# ALU_Flags.net
KiCad netlist of a schematic drawn in EAGLE
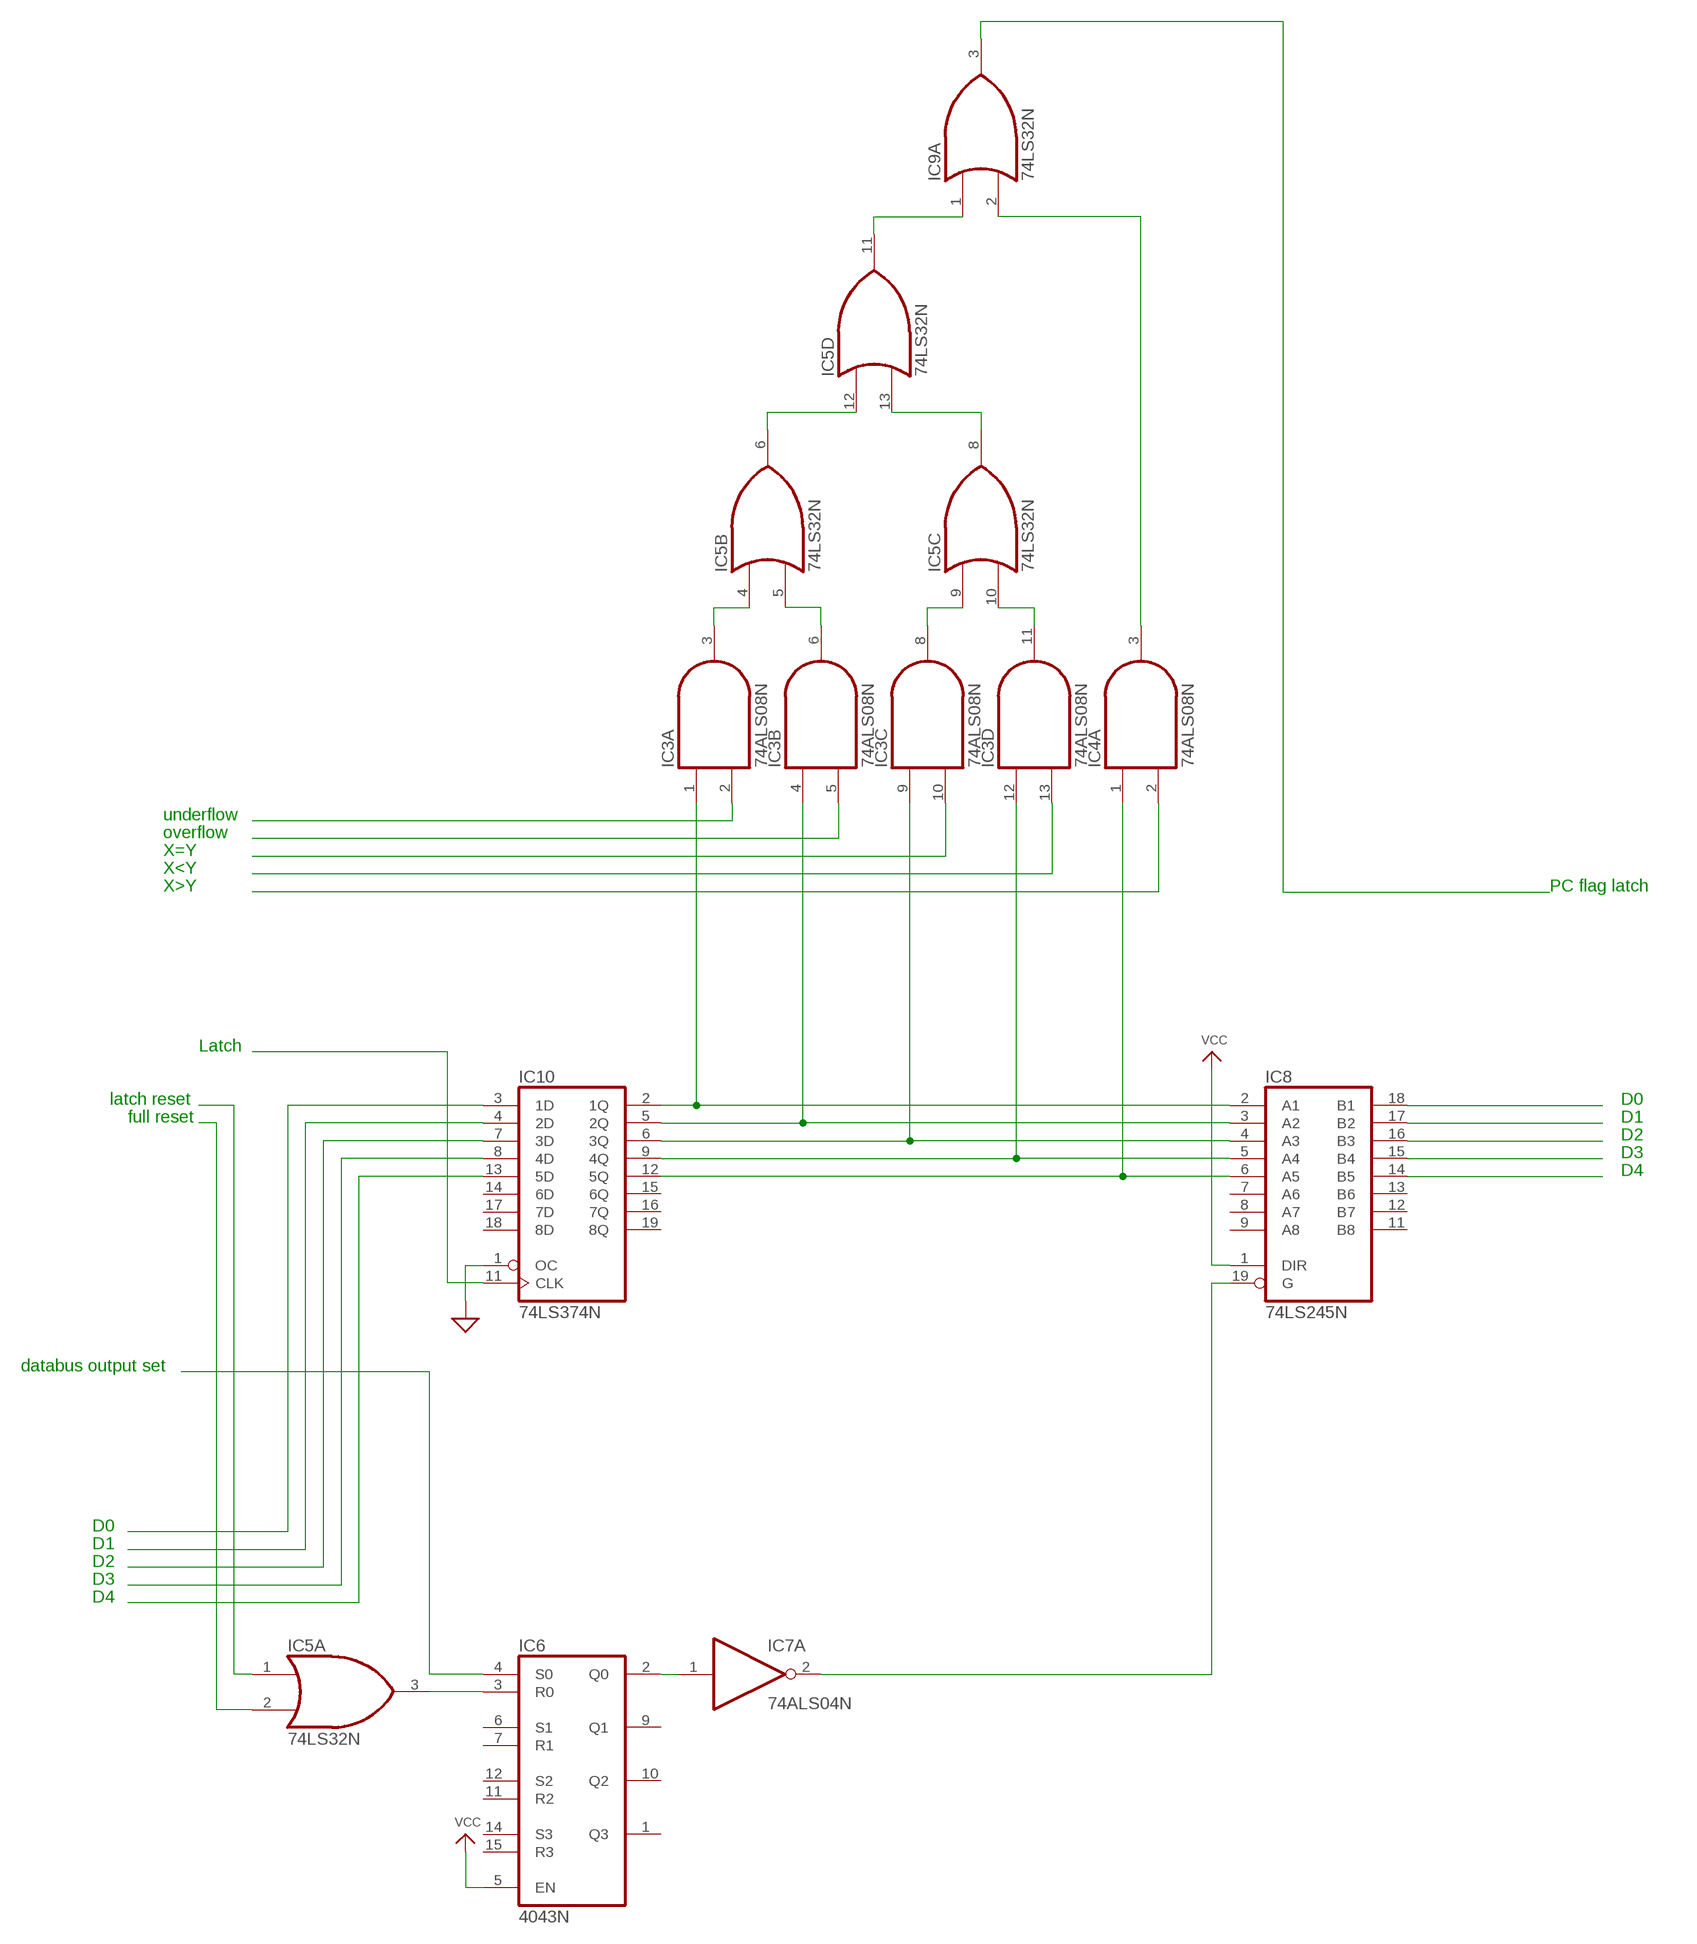
[diagram p0: schematic, sheet 1]

(export (version "E")
  (design (tool "Eeschema 10.0.6"))
  (components
    (comp (ref "IC3")
      (value "74ALS08N")
      (footprint "eagle-import:DIL14")
      (libsource (lib "eagle-import") (part "7408NALS"))
    )
    (comp (ref "IC4")
      (value "74ALS08N")
      (footprint "eagle-import:DIL14")
      (libsource (lib "eagle-import") (part "7408NALS"))
    )
    (comp (ref "IC5")
      (value "74LS32N")
      (footprint "eagle-import:DIL14")
      (libsource (lib "eagle-import") (part "7432NLS"))
    )
    (comp (ref "IC6")
      (value "4043N")
      (footprint "eagle-import:DIL16")
      (libsource (lib "eagle-import") (part "4043N"))
    )
    (comp (ref "IC7")
      (value "74ALS04N")
      (footprint "eagle-import:DIL14")
      (libsource (lib "eagle-import") (part "7404NALS"))
    )
    (comp (ref "IC8")
      (value "74LS245N")
      (footprint "eagle-import:DIL20")
      (libsource (lib "eagle-import") (part "74245NLS"))
    )
    (comp (ref "IC9")
      (value "74LS32N")
      (footprint "eagle-import:DIL14")
      (libsource (lib "eagle-import") (part "7432NLS"))
    )
    (comp (ref "IC10")
      (value "74LS374N")
      (footprint "eagle-import:DIL20")
      (libsource (lib "eagle-import") (part "74374NLS"))
    )
  )
  (nets
    (net (code "1") (name "Net-(IC3A-O)") (class "Default")
      (node (ref "IC3") (pin "3") (pinfunction "O_3") (pintype "output"))
      (node (ref "IC5") (pin "4") (pinfunction "I0_4") (pintype "input"))
    )
    (net (code "2") (name "Net-(IC3B-O)") (class "Default")
      (node (ref "IC3") (pin "6") (pinfunction "O_6") (pintype "output"))
      (node (ref "IC5") (pin "5") (pinfunction "I1_5") (pintype "input"))
    )
    (net (code "3") (name "Net-(IC3C-O)") (class "Default")
      (node (ref "IC3") (pin "8") (pinfunction "O_8") (pintype "output"))
      (node (ref "IC5") (pin "9") (pinfunction "I0_9") (pintype "input"))
    )
    (net (code "4") (name "Net-(IC3D-O)") (class "Default")
      (node (ref "IC3") (pin "11") (pinfunction "O_11") (pintype "output"))
      (node (ref "IC5") (pin "10") (pinfunction "I1_10") (pintype "input"))
    )
    (net (code "5") (name "Net-(IC4A-O)") (class "Default")
      (node (ref "IC4") (pin "3") (pinfunction "O_3") (pintype "output"))
      (node (ref "IC9") (pin "2") (pinfunction "I1_2") (pintype "input"))
    )
    (net (code "6") (name "Net-(IC5A-O)") (class "Default")
      (node (ref "IC5") (pin "3") (pinfunction "O_3") (pintype "output"))
      (node (ref "IC6") (pin "3") (pinfunction "R0_3") (pintype "input"))
    )
    (net (code "7") (name "Net-(IC5B-O)") (class "Default")
      (node (ref "IC5") (pin "12") (pinfunction "I0_12") (pintype "input"))
      (node (ref "IC5") (pin "6") (pinfunction "O_6") (pintype "output"))
    )
    (net (code "8") (name "Net-(IC5C-O)") (class "Default")
      (node (ref "IC5") (pin "13") (pinfunction "I1_13") (pintype "input"))
      (node (ref "IC5") (pin "8") (pinfunction "O_8") (pintype "output"))
    )
    (net (code "9") (name "Net-(IC5D-O)") (class "Default")
      (node (ref "IC5") (pin "11") (pinfunction "O_11") (pintype "output"))
      (node (ref "IC9") (pin "1") (pinfunction "I0_1") (pintype "input"))
    )
    (net (code "10") (name "Net-(IC6A-Q0)") (class "Default")
      (node (ref "IC6") (pin "2") (pinfunction "Q0_2") (pintype "output"))
      (node (ref "IC7") (pin "1") (pinfunction "I_1") (pintype "input"))
    )
    (net (code "11") (name "Net-(IC7A-O)") (class "Default")
      (node (ref "IC7") (pin "2") (pinfunction "O_2") (pintype "output"))
      (node (ref "IC8") (pin "19") (pinfunction "G_19") (pintype "input"))
    )
    (net (code "12") (name "Net-(IC10A-1Q)") (class "Default")
      (node (ref "IC10") (pin "2") (pinfunction "1Q_2") (pintype "tri_state"))
      (node (ref "IC3") (pin "1") (pinfunction "I0_1") (pintype "input"))
      (node (ref "IC8") (pin "2") (pinfunction "A1_2") (pintype "bidirectional"))
    )
    (net (code "13") (name "Net-(IC10A-2Q)") (class "Default")
      (node (ref "IC10") (pin "5") (pinfunction "2Q_5") (pintype "tri_state"))
      (node (ref "IC3") (pin "4") (pinfunction "I0_4") (pintype "input"))
      (node (ref "IC8") (pin "3") (pinfunction "A2_3") (pintype "bidirectional"))
    )
    (net (code "14") (name "Net-(IC10A-3Q)") (class "Default")
      (node (ref "IC10") (pin "6") (pinfunction "3Q_6") (pintype "tri_state"))
      (node (ref "IC3") (pin "9") (pinfunction "I0_9") (pintype "input"))
      (node (ref "IC8") (pin "4") (pinfunction "A3_4") (pintype "bidirectional"))
    )
    (net (code "15") (name "Net-(IC10A-4Q)") (class "Default")
      (node (ref "IC10") (pin "9") (pinfunction "4Q_9") (pintype "tri_state"))
      (node (ref "IC3") (pin "12") (pinfunction "I0_12") (pintype "input"))
      (node (ref "IC8") (pin "5") (pinfunction "A4_5") (pintype "bidirectional"))
    )
    (net (code "16") (name "Net-(IC10A-5Q)") (class "Default")
      (node (ref "IC10") (pin "12") (pinfunction "5Q_12") (pintype "tri_state"))
      (node (ref "IC4") (pin "1") (pinfunction "I0_1") (pintype "input"))
      (node (ref "IC8") (pin "6") (pinfunction "A5_6") (pintype "bidirectional"))
    )
    (net (code "17") (name "SUP") (class "Default")
      (node (ref "IC10") (pin "1") (pinfunction "OC_1") (pintype "input"))
    )
    (net (code "18") (name "VCC") (class "Default")
      (node (ref "IC6") (pin "5") (pinfunction "EN_5") (pintype "input"))
      (node (ref "IC8") (pin "1") (pinfunction "DIR_1") (pintype "input"))
    )
    (net (code "19") (name "unconnected-(IC3A-I1-Pad2)") (class "Default")
      (node (ref "IC3") (pin "2") (pinfunction "I1_2") (pintype "input"))
    )
    (net (code "20") (name "unconnected-(IC3B-I1-Pad5)") (class "Default")
      (node (ref "IC3") (pin "5") (pinfunction "I1_5") (pintype "input"))
    )
    (net (code "21") (name "unconnected-(IC3C-I1-Pad10)") (class "Default")
      (node (ref "IC3") (pin "10") (pinfunction "I1_10") (pintype "input"))
    )
    (net (code "22") (name "unconnected-(IC3D-I1-Pad13)") (class "Default")
      (node (ref "IC3") (pin "13") (pinfunction "I1_13") (pintype "input"))
    )
    (net (code "23") (name "unconnected-(IC4A-I1-Pad2)") (class "Default")
      (node (ref "IC4") (pin "2") (pinfunction "I1_2") (pintype "input"))
    )
    (net (code "24") (name "unconnected-(IC5A-I0-Pad1)") (class "Default")
      (node (ref "IC5") (pin "1") (pinfunction "I0_1") (pintype "input"))
    )
    (net (code "25") (name "unconnected-(IC5A-I1-Pad2)") (class "Default")
      (node (ref "IC5") (pin "2") (pinfunction "I1_2") (pintype "input"))
    )
    (net (code "26") (name "unconnected-(IC6A-Q1-Pad9)") (class "Default")
      (node (ref "IC6") (pin "9") (pinfunction "Q1_9") (pintype "output"))
    )
    (net (code "27") (name "unconnected-(IC6A-Q2-Pad10)") (class "Default")
      (node (ref "IC6") (pin "10") (pinfunction "Q2_10") (pintype "output"))
    )
    (net (code "28") (name "unconnected-(IC6A-Q3-Pad1)") (class "Default")
      (node (ref "IC6") (pin "1") (pinfunction "Q3_1") (pintype "output"))
    )
    (net (code "29") (name "unconnected-(IC6A-R1-Pad7)") (class "Default")
      (node (ref "IC6") (pin "7") (pinfunction "R1_7") (pintype "input"))
    )
    (net (code "30") (name "unconnected-(IC6A-R2-Pad11)") (class "Default")
      (node (ref "IC6") (pin "11") (pinfunction "R2_11") (pintype "input"))
    )
    (net (code "31") (name "unconnected-(IC6A-R3-Pad15)") (class "Default")
      (node (ref "IC6") (pin "15") (pinfunction "R3_15") (pintype "input"))
    )
    (net (code "32") (name "unconnected-(IC6A-S0-Pad4)") (class "Default")
      (node (ref "IC6") (pin "4") (pinfunction "S0_4") (pintype "input"))
    )
    (net (code "33") (name "unconnected-(IC6A-S1-Pad6)") (class "Default")
      (node (ref "IC6") (pin "6") (pinfunction "S1_6") (pintype "input"))
    )
    (net (code "34") (name "unconnected-(IC6A-S2-Pad12)") (class "Default")
      (node (ref "IC6") (pin "12") (pinfunction "S2_12") (pintype "input"))
    )
    (net (code "35") (name "unconnected-(IC6A-S3-Pad14)") (class "Default")
      (node (ref "IC6") (pin "14") (pinfunction "S3_14") (pintype "input"))
    )
    (net (code "36") (name "unconnected-(IC8A-A6-Pad7)") (class "Default")
      (node (ref "IC8") (pin "7") (pinfunction "A6_7") (pintype "bidirectional"))
    )
    (net (code "37") (name "unconnected-(IC8A-A7-Pad8)") (class "Default")
      (node (ref "IC8") (pin "8") (pinfunction "A7_8") (pintype "bidirectional"))
    )
    (net (code "38") (name "unconnected-(IC8A-A8-Pad9)") (class "Default")
      (node (ref "IC8") (pin "9") (pinfunction "A8_9") (pintype "bidirectional"))
    )
    (net (code "39") (name "unconnected-(IC8A-B1-Pad18)") (class "Default")
      (node (ref "IC8") (pin "18") (pinfunction "B1_18") (pintype "bidirectional"))
    )
    (net (code "40") (name "unconnected-(IC8A-B2-Pad17)") (class "Default")
      (node (ref "IC8") (pin "17") (pinfunction "B2_17") (pintype "bidirectional"))
    )
    (net (code "41") (name "unconnected-(IC8A-B3-Pad16)") (class "Default")
      (node (ref "IC8") (pin "16") (pinfunction "B3_16") (pintype "bidirectional"))
    )
    (net (code "42") (name "unconnected-(IC8A-B4-Pad15)") (class "Default")
      (node (ref "IC8") (pin "15") (pinfunction "B4_15") (pintype "bidirectional"))
    )
    (net (code "43") (name "unconnected-(IC8A-B5-Pad14)") (class "Default")
      (node (ref "IC8") (pin "14") (pinfunction "B5_14") (pintype "bidirectional"))
    )
    (net (code "44") (name "unconnected-(IC8A-B6-Pad13)") (class "Default")
      (node (ref "IC8") (pin "13") (pinfunction "B6_13") (pintype "bidirectional"))
    )
    (net (code "45") (name "unconnected-(IC8A-B7-Pad12)") (class "Default")
      (node (ref "IC8") (pin "12") (pinfunction "B7_12") (pintype "bidirectional"))
    )
    (net (code "46") (name "unconnected-(IC8A-B8-Pad11)") (class "Default")
      (node (ref "IC8") (pin "11") (pinfunction "B8_11") (pintype "bidirectional"))
    )
    (net (code "47") (name "unconnected-(IC9A-O-Pad3)") (class "Default")
      (node (ref "IC9") (pin "3") (pinfunction "O_3") (pintype "output"))
    )
    (net (code "48") (name "unconnected-(IC10A-1D-Pad3)") (class "Default")
      (node (ref "IC10") (pin "3") (pinfunction "1D_3") (pintype "input"))
    )
    (net (code "49") (name "unconnected-(IC10A-2D-Pad4)") (class "Default")
      (node (ref "IC10") (pin "4") (pinfunction "2D_4") (pintype "input"))
    )
    (net (code "50") (name "unconnected-(IC10A-3D-Pad7)") (class "Default")
      (node (ref "IC10") (pin "7") (pinfunction "3D_7") (pintype "input"))
    )
    (net (code "51") (name "unconnected-(IC10A-4D-Pad8)") (class "Default")
      (node (ref "IC10") (pin "8") (pinfunction "4D_8") (pintype "input"))
    )
    (net (code "52") (name "unconnected-(IC10A-5D-Pad13)") (class "Default")
      (node (ref "IC10") (pin "13") (pinfunction "5D_13") (pintype "input"))
    )
    (net (code "53") (name "unconnected-(IC10A-6D-Pad14)") (class "Default")
      (node (ref "IC10") (pin "14") (pinfunction "6D_14") (pintype "input"))
    )
    (net (code "54") (name "unconnected-(IC10A-6Q-Pad15)") (class "Default")
      (node (ref "IC10") (pin "15") (pinfunction "6Q_15") (pintype "tri_state"))
    )
    (net (code "55") (name "unconnected-(IC10A-7D-Pad17)") (class "Default")
      (node (ref "IC10") (pin "17") (pinfunction "7D_17") (pintype "input"))
    )
    (net (code "56") (name "unconnected-(IC10A-7Q-Pad16)") (class "Default")
      (node (ref "IC10") (pin "16") (pinfunction "7Q_16") (pintype "tri_state"))
    )
    (net (code "57") (name "unconnected-(IC10A-8D-Pad18)") (class "Default")
      (node (ref "IC10") (pin "18") (pinfunction "8D_18") (pintype "input"))
    )
    (net (code "58") (name "unconnected-(IC10A-8Q-Pad19)") (class "Default")
      (node (ref "IC10") (pin "19") (pinfunction "8Q_19") (pintype "tri_state"))
    )
    (net (code "59") (name "unconnected-(IC10A-CLK-Pad11)") (class "Default")
      (node (ref "IC10") (pin "11") (pinfunction "CLK_11") (pintype "input"))
    )
  )
)
